# Sensor_Circuit.net
KiCad netlist of a schematic drawn in EAGLE
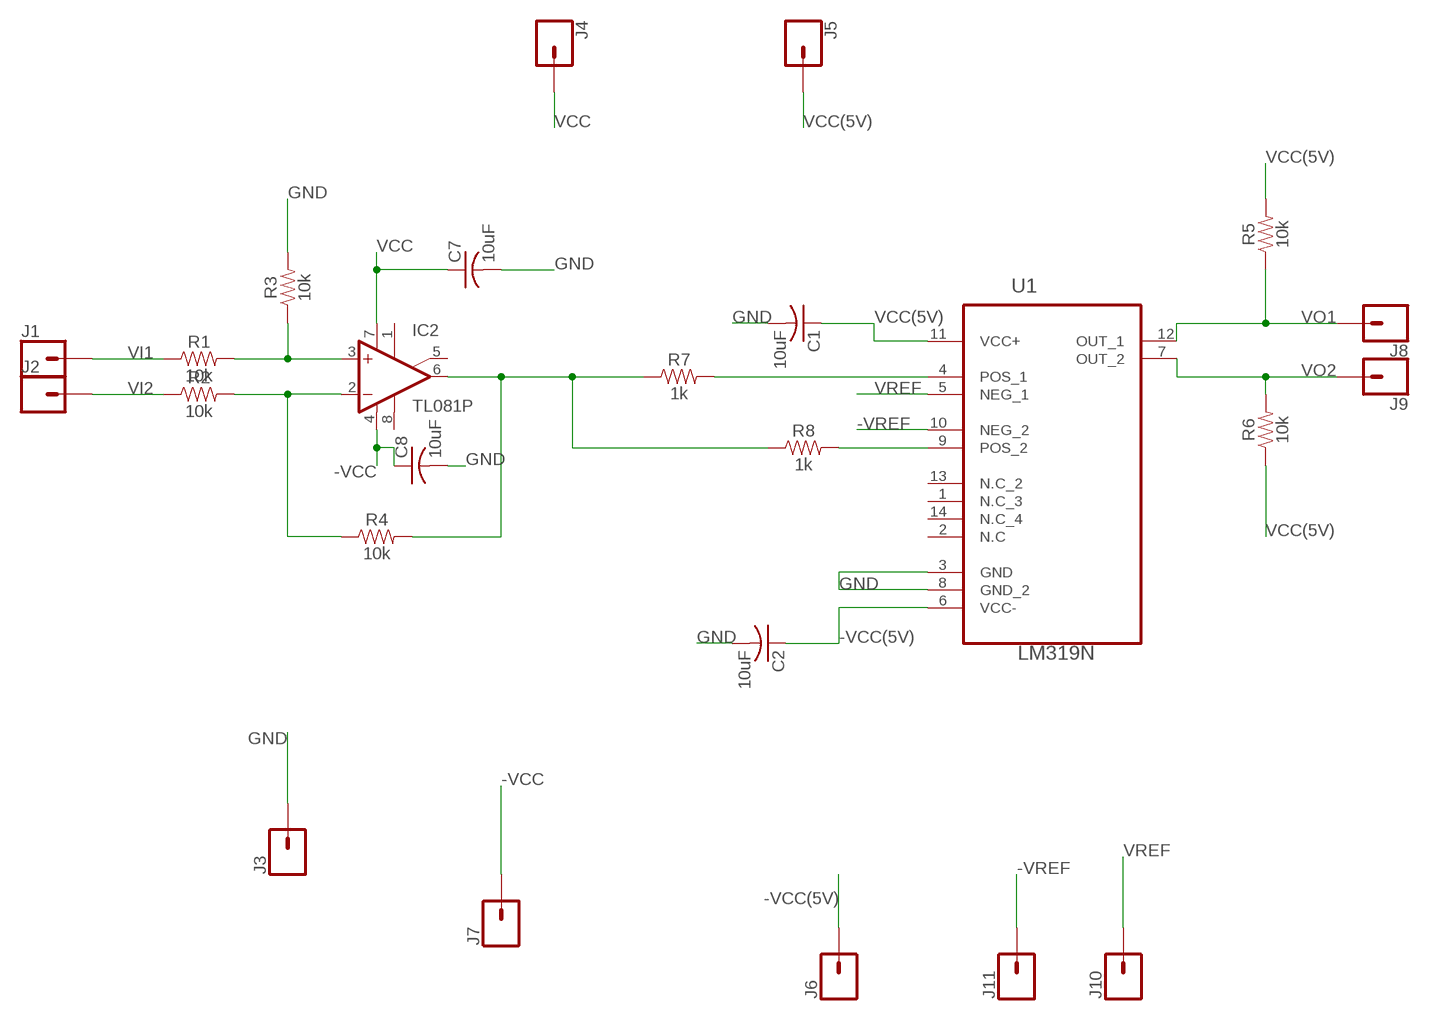
[diagram p0: schematic, sheet 1]

(export (version "E")
  (design (tool "Eeschema 10.0.6"))
  (components
    (comp (ref "C1")
      (value "10uF")
      (footprint "eagle-import:C050-024X044")
      (libsource (lib "eagle-import") (part "C-US050-024X044"))
    )
    (comp (ref "C2")
      (value "10uF")
      (footprint "eagle-import:C050-024X044")
      (libsource (lib "eagle-import") (part "C-US050-024X044"))
    )
    (comp (ref "C7")
      (value "10uF")
      (footprint "eagle-import:C050-024X044")
      (libsource (lib "eagle-import") (part "C-US050-024X044"))
    )
    (comp (ref "C8")
      (value "10uF")
      (footprint "eagle-import:C050-024X044")
      (libsource (lib "eagle-import") (part "C-US050-024X044"))
    )
    (comp (ref "IC2")
      (value "TL081P")
      (footprint "eagle-import:DIL08")
      (fields (field (name "MF") "Texas Instruments") (field (name "MP") "TL081"))
      (libsource (lib "eagle-import") (part "TL081P"))
    )
    (comp (ref "J1")
      (value "CONN_01")
      (footprint "eagle-import:1X01")
      (libsource (lib "eagle-import") (part "CONN_01"))
    )
    (comp (ref "J2")
      (value "CONN_01")
      (footprint "eagle-import:1X01")
      (libsource (lib "eagle-import") (part "CONN_01"))
    )
    (comp (ref "J3")
      (value "CONN_01")
      (footprint "eagle-import:1X01")
      (libsource (lib "eagle-import") (part "CONN_01"))
    )
    (comp (ref "J4")
      (value "CONN_01")
      (footprint "eagle-import:1X01")
      (libsource (lib "eagle-import") (part "CONN_01"))
    )
    (comp (ref "J5")
      (value "CONN_01")
      (footprint "eagle-import:1X01")
      (libsource (lib "eagle-import") (part "CONN_01"))
    )
    (comp (ref "J6")
      (value "CONN_01")
      (footprint "eagle-import:1X01")
      (libsource (lib "eagle-import") (part "CONN_01"))
    )
    (comp (ref "J7")
      (value "CONN_01")
      (footprint "eagle-import:1X01")
      (libsource (lib "eagle-import") (part "CONN_01"))
    )
    (comp (ref "J8")
      (value "CONN_01")
      (footprint "eagle-import:1X01")
      (libsource (lib "eagle-import") (part "CONN_01"))
    )
    (comp (ref "J9")
      (value "CONN_01")
      (footprint "eagle-import:1X01")
      (libsource (lib "eagle-import") (part "CONN_01"))
    )
    (comp (ref "J10")
      (value "CONN_01")
      (footprint "eagle-import:1X01")
      (libsource (lib "eagle-import") (part "CONN_01"))
    )
    (comp (ref "J11")
      (value "CONN_01")
      (footprint "eagle-import:1X01")
      (libsource (lib "eagle-import") (part "CONN_01"))
    )
    (comp (ref "R1")
      (value "10k")
      (footprint "eagle-import:AXIAL-0.3")
      (libsource (lib "eagle-import") (part "10KOHM-HORIZ-1/4W-1%"))
    )
    (comp (ref "R2")
      (value "10k")
      (footprint "eagle-import:AXIAL-0.3")
      (libsource (lib "eagle-import") (part "10KOHM-HORIZ-1/4W-1%"))
    )
    (comp (ref "R3")
      (value "10k")
      (footprint "eagle-import:AXIAL-0.3")
      (libsource (lib "eagle-import") (part "10KOHM-HORIZ-1/4W-1%"))
    )
    (comp (ref "R4")
      (value "10k")
      (footprint "eagle-import:AXIAL-0.3")
      (libsource (lib "eagle-import") (part "10KOHM-HORIZ-1/4W-1%"))
    )
    (comp (ref "R5")
      (value "10k")
      (footprint "eagle-import:AXIAL-0.3")
      (libsource (lib "eagle-import") (part "10KOHM-HORIZ-1/4W-1%"))
    )
    (comp (ref "R6")
      (value "10k")
      (footprint "eagle-import:AXIAL-0.3")
      (libsource (lib "eagle-import") (part "10KOHM-HORIZ-1/4W-1%"))
    )
    (comp (ref "R7")
      (value "1k")
      (footprint "eagle-import:AXIAL-0.3")
      (libsource (lib "eagle-import") (part "1KOHM-HORIZ-1/4W-1%"))
    )
    (comp (ref "R8")
      (value "1k")
      (footprint "eagle-import:AXIAL-0.3")
      (libsource (lib "eagle-import") (part "1KOHM-HORIZ-1/4W-1%"))
    )
    (comp (ref "U1")
      (value "LM319N")
      (footprint "eagle-import:DIP254P762X510-14")
      (fields (field (name "MF") "Texas Instruments") (field (name "MP") "LM319N/NOPB"))
      (libsource (lib "eagle-import") (part "LM319N"))
    )
  )
  (nets
    (net (code "1") (name "/-VCC") (class "Default")
      (node (ref "C8") (pin "1") (pinfunction "1_1") (pintype "passive"))
      (node (ref "IC2") (pin "4") (pinfunction "V-_4") (pintype "power_in"))
      (node (ref "J7") (pin "1") (pinfunction "1_1") (pintype "passive"))
    )
    (net (code "2") (name "/-VCC(5V)") (class "Default")
      (node (ref "C2") (pin "1") (pinfunction "1_1") (pintype "passive"))
      (node (ref "J6") (pin "1") (pinfunction "1_1") (pintype "passive"))
      (node (ref "U1") (pin "6") (pinfunction "VCC-_6") (pintype "power_in"))
    )
    (net (code "3") (name "/-VREF") (class "Default")
      (node (ref "J11") (pin "1") (pinfunction "1_1") (pintype "passive"))
      (node (ref "U1") (pin "10") (pinfunction "NEG_2_10") (pintype "input"))
    )
    (net (code "4") (name "/GND") (class "Default")
      (node (ref "C1") (pin "2") (pinfunction "2_2") (pintype "passive"))
      (node (ref "C2") (pin "2") (pinfunction "2_2") (pintype "passive"))
      (node (ref "C7") (pin "2") (pinfunction "2_2") (pintype "passive"))
      (node (ref "C8") (pin "2") (pinfunction "2_2") (pintype "passive"))
      (node (ref "J3") (pin "1") (pinfunction "1_1") (pintype "passive"))
      (node (ref "R3") (pin "P$2") (pinfunction "2_P$2") (pintype "passive"))
      (node (ref "U1") (pin "3") (pinfunction "GND_3") (pintype "passive"))
      (node (ref "U1") (pin "8") (pinfunction "GND_2_8") (pintype "passive"))
    )
    (net (code "5") (name "/VCC") (class "Default")
      (node (ref "C7") (pin "1") (pinfunction "1_1") (pintype "passive"))
      (node (ref "IC2") (pin "7") (pinfunction "V+_7") (pintype "power_in"))
      (node (ref "J4") (pin "1") (pinfunction "1_1") (pintype "passive"))
    )
    (net (code "6") (name "/VCC(5V)") (class "Default")
      (node (ref "C1") (pin "1") (pinfunction "1_1") (pintype "passive"))
      (node (ref "J5") (pin "1") (pinfunction "1_1") (pintype "passive"))
      (node (ref "R5") (pin "P$2") (pinfunction "2_P$2") (pintype "passive"))
      (node (ref "R6") (pin "P$1") (pinfunction "1_P$1") (pintype "passive"))
      (node (ref "U1") (pin "11") (pinfunction "VCC+_11") (pintype "power_in"))
    )
    (net (code "7") (name "/VI1") (class "Default")
      (node (ref "J1") (pin "1") (pinfunction "1_1") (pintype "passive"))
      (node (ref "R1") (pin "P$1") (pinfunction "1_P$1") (pintype "passive"))
    )
    (net (code "8") (name "/VI2") (class "Default")
      (node (ref "J2") (pin "1") (pinfunction "1_1") (pintype "passive"))
      (node (ref "R2") (pin "P$1") (pinfunction "1_P$1") (pintype "passive"))
    )
    (net (code "9") (name "/VO1") (class "Default")
      (node (ref "J8") (pin "1") (pinfunction "1_1") (pintype "passive"))
      (node (ref "R5") (pin "P$1") (pinfunction "1_P$1") (pintype "passive"))
      (node (ref "U1") (pin "12") (pinfunction "OUT_1_12") (pintype "output"))
    )
    (net (code "10") (name "/VO2") (class "Default")
      (node (ref "J9") (pin "1") (pinfunction "1_1") (pintype "passive"))
      (node (ref "R6") (pin "P$2") (pinfunction "2_P$2") (pintype "passive"))
      (node (ref "U1") (pin "7") (pinfunction "OUT_2_7") (pintype "output"))
    )
    (net (code "11") (name "/VREF") (class "Default")
      (node (ref "J10") (pin "1") (pinfunction "1_1") (pintype "passive"))
      (node (ref "U1") (pin "5") (pinfunction "NEG_1_5") (pintype "input"))
    )
    (net (code "12") (name "Net-(IC2-+IN)") (class "Default")
      (node (ref "IC2") (pin "3") (pinfunction "+IN_3") (pintype "input"))
      (node (ref "R1") (pin "P$2") (pinfunction "2_P$2") (pintype "passive"))
      (node (ref "R3") (pin "P$1") (pinfunction "1_P$1") (pintype "passive"))
    )
    (net (code "13") (name "Net-(IC2--IN)") (class "Default")
      (node (ref "IC2") (pin "2") (pinfunction "-IN_2") (pintype "input"))
      (node (ref "R2") (pin "P$2") (pinfunction "2_P$2") (pintype "passive"))
      (node (ref "R4") (pin "P$1") (pinfunction "1_P$1") (pintype "passive"))
    )
    (net (code "14") (name "Net-(IC2-OUT)") (class "Default")
      (node (ref "IC2") (pin "6") (pinfunction "OUT_6") (pintype "output"))
      (node (ref "R4") (pin "P$2") (pinfunction "2_P$2") (pintype "passive"))
      (node (ref "R7") (pin "P$1") (pinfunction "1_P$1") (pintype "passive"))
      (node (ref "R8") (pin "P$1") (pinfunction "1_P$1") (pintype "passive"))
    )
    (net (code "15") (name "Net-(R7-2)") (class "Default")
      (node (ref "R7") (pin "P$2") (pinfunction "2_P$2") (pintype "passive"))
      (node (ref "U1") (pin "4") (pinfunction "POS_1_4") (pintype "input"))
    )
    (net (code "16") (name "Net-(R8-2)") (class "Default")
      (node (ref "R8") (pin "P$2") (pinfunction "2_P$2") (pintype "passive"))
      (node (ref "U1") (pin "9") (pinfunction "POS_2_9") (pintype "input"))
    )
    (net (code "17") (name "unconnected-(IC2-ON1-Pad1)") (class "Default")
      (node (ref "IC2") (pin "1") (pinfunction "ON1_1") (pintype "passive"))
    )
    (net (code "18") (name "unconnected-(IC2-ON2-Pad5)") (class "Default")
      (node (ref "IC2") (pin "5") (pinfunction "ON2_5") (pintype "passive"))
    )
    (net (code "19") (name "unconnected-(IC2-OPT-Pad8)") (class "Default")
      (node (ref "IC2") (pin "8") (pinfunction "OPT_8") (pintype "passive"))
    )
    (net (code "20") (name "unconnected-(U1-N.C-Pad2)") (class "Default")
      (node (ref "U1") (pin "2") (pinfunction "N.C_2") (pintype "no_connect"))
    )
    (net (code "21") (name "unconnected-(U1-N.C_2-Pad13)") (class "Default")
      (node (ref "U1") (pin "13") (pinfunction "N.C_2_13") (pintype "no_connect"))
    )
    (net (code "22") (name "unconnected-(U1-N.C_3-Pad1)") (class "Default")
      (node (ref "U1") (pin "1") (pinfunction "N.C_3_1") (pintype "no_connect"))
    )
    (net (code "23") (name "unconnected-(U1-N.C_4-Pad14)") (class "Default")
      (node (ref "U1") (pin "14") (pinfunction "N.C_4_14") (pintype "no_connect"))
    )
  )
)
